# Gate_main.net
KiCad netlist of a schematic drawn in EAGLE
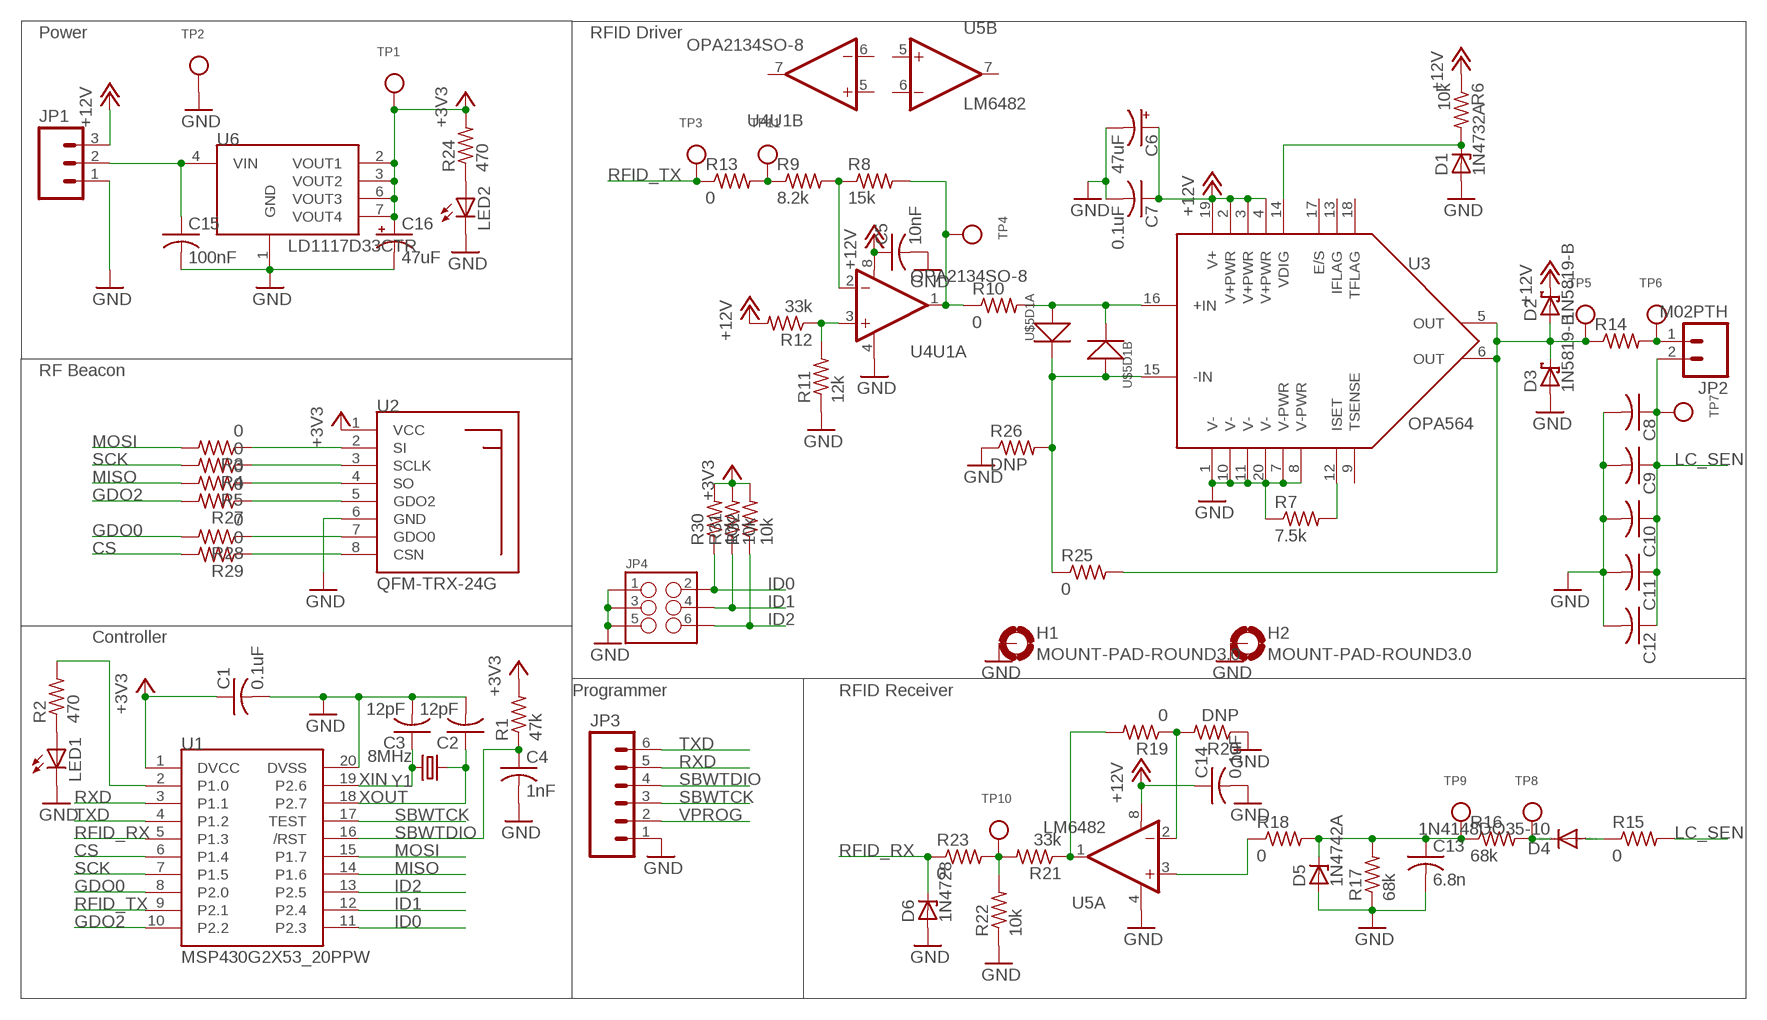
[diagram p0: schematic, sheet 1]

(export (version "E")
  (design (tool "Eeschema 10.0.6"))
  (components
    (comp (ref "C1")
      (value "0.1uF")
      (footprint "eagle-import:C0805")
      (libsource (lib "eagle-import") (part "C-USC0805"))
    )
    (comp (ref "C2")
      (value "12pF")
      (footprint "eagle-import:C0805")
      (libsource (lib "eagle-import") (part "C-USC0805"))
    )
    (comp (ref "C3")
      (value "12pF")
      (footprint "eagle-import:C0805")
      (libsource (lib "eagle-import") (part "C-USC0805"))
    )
    (comp (ref "C4")
      (value "1nF")
      (footprint "eagle-import:C0805")
      (libsource (lib "eagle-import") (part "C-USC0805"))
    )
    (comp (ref "C5")
      (value "10nF")
      (footprint "eagle-import:C0805")
      (libsource (lib "eagle-import") (part "C-USC0805"))
    )
    (comp (ref "C6")
      (value "47uF")
      (footprint "eagle-import:E2,5-6")
      (libsource (lib "eagle-import") (part "CPOL-USE2.5-6"))
    )
    (comp (ref "C7")
      (value "0.1uF")
      (footprint "eagle-import:C0805")
      (libsource (lib "eagle-import") (part "C-USC0805"))
    )
    (comp (ref "C8")
      (value "C-USC0805")
      (footprint "eagle-import:C0805")
      (libsource (lib "eagle-import") (part "C-USC0805"))
    )
    (comp (ref "C9")
      (value "C-USC0805")
      (footprint "eagle-import:C0805")
      (libsource (lib "eagle-import") (part "C-USC0805"))
    )
    (comp (ref "C10")
      (value "C-USC0805")
      (footprint "eagle-import:C0805")
      (libsource (lib "eagle-import") (part "C-USC0805"))
    )
    (comp (ref "C11")
      (value "C-USC0805")
      (footprint "eagle-import:C0805")
      (libsource (lib "eagle-import") (part "C-USC0805"))
    )
    (comp (ref "C12")
      (value "C-USC0805")
      (footprint "eagle-import:C0805")
      (libsource (lib "eagle-import") (part "C-USC0805"))
    )
    (comp (ref "C13")
      (value "6.8n")
      (footprint "eagle-import:C0805")
      (libsource (lib "eagle-import") (part "C-USC0805"))
    )
    (comp (ref "C14")
      (value "0.1uF")
      (footprint "eagle-import:C0805")
      (libsource (lib "eagle-import") (part "C-USC0805"))
    )
    (comp (ref "C15")
      (value "100nF")
      (footprint "eagle-import:C0805")
      (libsource (lib "eagle-import") (part "C-USC0805"))
    )
    (comp (ref "C16")
      (value "47uF")
      (footprint "eagle-import:E2,5-6")
      (libsource (lib "eagle-import") (part "CPOL-USE2.5-6"))
    )
    (comp (ref "D1")
      (value "1N4732A")
      (footprint "eagle-import:DO41Z10")
      (libsource (lib "eagle-import") (part "1N4728"))
    )
    (comp (ref "D2")
      (value "1N5819-B")
      (footprint "eagle-import:DO41-7.6")
      (libsource (lib "eagle-import") (part "1N5819-B"))
    )
    (comp (ref "D3")
      (value "1N5819-B")
      (footprint "eagle-import:DO41-7.6")
      (libsource (lib "eagle-import") (part "1N5819-B"))
    )
    (comp (ref "D4")
      (value "1N4148DO35-10")
      (footprint "eagle-import:DO35-10")
      (libsource (lib "eagle-import") (part "1N4148DO35-10"))
    )
    (comp (ref "D5")
      (value "1N4742A")
      (footprint "eagle-import:DO41Z10")
      (libsource (lib "eagle-import") (part "1N4728"))
    )
    (comp (ref "D6")
      (value "1N4728")
      (footprint "eagle-import:DO41Z10")
      (libsource (lib "eagle-import") (part "1N4728"))
    )
    (comp (ref "H1")
      (value "MOUNT-PAD-ROUND3.0")
      (footprint "eagle-import:3,0-PAD")
      (libsource (lib "eagle-import") (part "MOUNT-PAD-ROUND3.0"))
    )
    (comp (ref "H2")
      (value "MOUNT-PAD-ROUND3.0")
      (footprint "eagle-import:3,0-PAD")
      (libsource (lib "eagle-import") (part "MOUNT-PAD-ROUND3.0"))
    )
    (comp (ref "JP1")
      (value "M03PTH")
      (footprint "eagle-import:1X03")
      (libsource (lib "eagle-import") (part "M03PTH"))
    )
    (comp (ref "JP2")
      (value "M02PTH")
      (footprint "eagle-import:1X02")
      (libsource (lib "eagle-import") (part "M02PTH"))
    )
    (comp (ref "JP3")
      (value "M06SIP")
      (footprint "eagle-import:1X06")
      (libsource (lib "eagle-import") (part "M06SIP"))
    )
    (comp (ref "JP4")
      (value "M03X22X3_SILK_SM")
      (footprint "eagle-import:2X3")
      (libsource (lib "eagle-import") (part "M03X22X3_SILK_SM"))
    )
    (comp (ref "LED1")
      (value "LEDCHIPLED_0603")
      (footprint "eagle-import:CHIPLED_0603")
      (libsource (lib "eagle-import") (part "LEDCHIPLED_0603"))
    )
    (comp (ref "LED2")
      (value "LEDCHIPLED_0603")
      (footprint "eagle-import:CHIPLED_0603")
      (libsource (lib "eagle-import") (part "LEDCHIPLED_0603"))
    )
    (comp (ref "R1")
      (value "47k")
      (footprint "eagle-import:R0805")
      (libsource (lib "eagle-import") (part "R-US_R0805"))
    )
    (comp (ref "R2")
      (value "470")
      (footprint "eagle-import:R0805")
      (libsource (lib "eagle-import") (part "R-US_R0805"))
    )
    (comp (ref "R3")
      (value "0")
      (footprint "eagle-import:R0805")
      (libsource (lib "eagle-import") (part "R-US_R0805"))
    )
    (comp (ref "R4")
      (value "0")
      (footprint "eagle-import:R0805")
      (libsource (lib "eagle-import") (part "R-US_R0805"))
    )
    (comp (ref "R5")
      (value "0")
      (footprint "eagle-import:R0805")
      (libsource (lib "eagle-import") (part "R-US_R0805"))
    )
    (comp (ref "R6")
      (value "10k")
      (footprint "eagle-import:R0805")
      (libsource (lib "eagle-import") (part "R-US_R0805"))
    )
    (comp (ref "R7")
      (value "7.5k")
      (footprint "eagle-import:R0805")
      (libsource (lib "eagle-import") (part "R-US_R0805"))
    )
    (comp (ref "R8")
      (value "15k")
      (footprint "eagle-import:R0805")
      (libsource (lib "eagle-import") (part "R-US_R0805"))
    )
    (comp (ref "R9")
      (value "8.2k")
      (footprint "eagle-import:R0805")
      (libsource (lib "eagle-import") (part "R-US_R0805"))
    )
    (comp (ref "R10")
      (value "0")
      (footprint "eagle-import:R0805")
      (libsource (lib "eagle-import") (part "R-US_R0805"))
    )
    (comp (ref "R11")
      (value "12k")
      (footprint "eagle-import:R0805")
      (libsource (lib "eagle-import") (part "R-US_R0805"))
    )
    (comp (ref "R12")
      (value "33k")
      (footprint "eagle-import:R0805")
      (libsource (lib "eagle-import") (part "R-US_R0805"))
    )
    (comp (ref "R13")
      (value "0")
      (footprint "eagle-import:R0805")
      (libsource (lib "eagle-import") (part "R-US_R0805"))
    )
    (comp (ref "R14")
      (value "R-US_0207/10")
      (footprint "eagle-import:0207_10")
      (libsource (lib "eagle-import") (part "R-US_0207/10"))
    )
    (comp (ref "R15")
      (value "0")
      (footprint "eagle-import:R0805")
      (libsource (lib "eagle-import") (part "R-US_R0805"))
    )
    (comp (ref "R16")
      (value "68k")
      (footprint "eagle-import:R0805")
      (libsource (lib "eagle-import") (part "R-US_R0805"))
    )
    (comp (ref "R17")
      (value "68k")
      (footprint "eagle-import:R0805")
      (libsource (lib "eagle-import") (part "R-US_R0805"))
    )
    (comp (ref "R18")
      (value "0")
      (footprint "eagle-import:R0805")
      (libsource (lib "eagle-import") (part "R-US_R0805"))
    )
    (comp (ref "R19")
      (value "0")
      (footprint "eagle-import:R0805")
      (libsource (lib "eagle-import") (part "R-US_R0805"))
    )
    (comp (ref "R20")
      (value "DNP")
      (footprint "eagle-import:R0805")
      (libsource (lib "eagle-import") (part "R-US_R0805"))
    )
    (comp (ref "R21")
      (value "33k")
      (footprint "eagle-import:R0805")
      (libsource (lib "eagle-import") (part "R-US_R0805"))
    )
    (comp (ref "R22")
      (value "10k")
      (footprint "eagle-import:R0805")
      (libsource (lib "eagle-import") (part "R-US_R0805"))
    )
    (comp (ref "R23")
      (value "0")
      (footprint "eagle-import:R0805")
      (libsource (lib "eagle-import") (part "R-US_R0805"))
    )
    (comp (ref "R24")
      (value "470")
      (footprint "eagle-import:R0805")
      (libsource (lib "eagle-import") (part "R-US_R0805"))
    )
    (comp (ref "R25")
      (value "0")
      (footprint "eagle-import:R0805")
      (libsource (lib "eagle-import") (part "R-US_R0805"))
    )
    (comp (ref "R26")
      (value "DNP")
      (footprint "eagle-import:R0805")
      (libsource (lib "eagle-import") (part "R-US_R0805"))
    )
    (comp (ref "R27")
      (value "0")
      (footprint "eagle-import:R0805")
      (libsource (lib "eagle-import") (part "R-US_R0805"))
    )
    (comp (ref "R28")
      (value "0")
      (footprint "eagle-import:R0805")
      (libsource (lib "eagle-import") (part "R-US_R0805"))
    )
    (comp (ref "R29")
      (value "0")
      (footprint "eagle-import:R0805")
      (libsource (lib "eagle-import") (part "R-US_R0805"))
    )
    (comp (ref "R30")
      (value "10k")
      (footprint "eagle-import:R0805")
      (libsource (lib "eagle-import") (part "R-US_R0805"))
    )
    (comp (ref "R31")
      (value "10k")
      (footprint "eagle-import:R0805")
      (libsource (lib "eagle-import") (part "R-US_R0805"))
    )
    (comp (ref "R32")
      (value "10k")
      (footprint "eagle-import:R0805")
      (libsource (lib "eagle-import") (part "R-US_R0805"))
    )
    (comp (ref "TP1")
      (value "TESTPOINT0.1\"")
      (footprint "eagle-import:1X01_ROUND")
      (libsource (lib "eagle-import") (part "TESTPOINT0.1{dblquote}"))
    )
    (comp (ref "TP2")
      (value "TESTPOINT0.1\"")
      (footprint "eagle-import:1X01_ROUND")
      (libsource (lib "eagle-import") (part "TESTPOINT0.1{dblquote}"))
    )
    (comp (ref "TP3")
      (value "TESTPOINT0.1\"")
      (footprint "eagle-import:1X01_ROUND")
      (libsource (lib "eagle-import") (part "TESTPOINT0.1{dblquote}"))
    )
    (comp (ref "TP4")
      (value "TESTPOINT0.1\"")
      (footprint "eagle-import:1X01_ROUND")
      (libsource (lib "eagle-import") (part "TESTPOINT0.1{dblquote}"))
    )
    (comp (ref "TP5")
      (value "TESTPOINT0.1\"")
      (footprint "eagle-import:1X01_ROUND")
      (libsource (lib "eagle-import") (part "TESTPOINT0.1{dblquote}"))
    )
    (comp (ref "TP6")
      (value "TESTPOINT0.1\"")
      (footprint "eagle-import:1X01_ROUND")
      (libsource (lib "eagle-import") (part "TESTPOINT0.1{dblquote}"))
    )
    (comp (ref "TP7")
      (value "TESTPOINT0.1\"")
      (footprint "eagle-import:1X01_ROUND")
      (libsource (lib "eagle-import") (part "TESTPOINT0.1{dblquote}"))
    )
    (comp (ref "TP8")
      (value "TESTPOINT0.1\"")
      (footprint "eagle-import:1X01_ROUND")
      (libsource (lib "eagle-import") (part "TESTPOINT0.1{dblquote}"))
    )
    (comp (ref "TP9")
      (value "TESTPOINT0.1\"")
      (footprint "eagle-import:1X01_ROUND")
      (libsource (lib "eagle-import") (part "TESTPOINT0.1{dblquote}"))
    )
    (comp (ref "TP10")
      (value "TESTPOINT0.1\"")
      (footprint "eagle-import:1X01_ROUND")
      (libsource (lib "eagle-import") (part "TESTPOINT0.1{dblquote}"))
    )
    (comp (ref "TP11")
      (value "TESTPOINT0.1\"")
      (footprint "eagle-import:1X01_ROUND")
      (libsource (lib "eagle-import") (part "TESTPOINT0.1{dblquote}"))
    )
    (comp (ref "U$5")
      (value "SMS3922-015LF")
      (footprint "eagle-import:SMS3922-015LF")
      (libsource (lib "eagle-import") (part "SMS3922-015LF"))
    )
    (comp (ref "U1")
      (value "MSP430G2X53_20PPW")
      (footprint "eagle-import:PW(R-PDSO-G20)")
      (libsource (lib "eagle-import") (part "MSP430G2X53_20PPW"))
    )
    (comp (ref "U2")
      (value "QFM-TRX-24G")
      (footprint "eagle-import:QFM-TRX1-24G")
      (libsource (lib "eagle-import") (part "QFM-TRX-24G"))
    )
    (comp (ref "U3")
      (value "OPA564")
      (footprint "eagle-import:SO-20LD")
      (libsource (lib "eagle-import") (part "OPA564"))
    )
    (comp (ref "U4")
      (value "OPA2134SO-8")
      (footprint "eagle-import:SOIC8")
      (libsource (lib "eagle-import") (part "OPA2134SO-8"))
    )
    (comp (ref "U5")
      (value "LM6482")
      (footprint "eagle-import:SOIC8")
      (libsource (lib "eagle-import") (part "LM6482"))
    )
    (comp (ref "U6")
      (value "LD1117D33CTR")
      (footprint "eagle-import:SOIC8")
      (libsource (lib "eagle-import") (part "LD1117D33CTR"))
    )
    (comp (ref "Y1")
      (value "8MHz")
      (footprint "eagle-import:HC49U-V")
      (libsource (lib "eagle-import") (part "CRYSTALHC49UV"))
    )
  )
  (nets
    (net (code "1") (name "+3V3") (class "Default")
      (node (ref "C1") (pin "1") (pinfunction "1_1") (pintype "passive"))
      (node (ref "C16") (pin "+") (pinfunction "+_+") (pintype "passive"))
      (node (ref "R1") (pin "2") (pinfunction "2_2") (pintype "passive"))
      (node (ref "R24") (pin "2") (pinfunction "2_2") (pintype "passive"))
      (node (ref "R30") (pin "2") (pinfunction "2_2") (pintype "passive"))
      (node (ref "R31") (pin "2") (pinfunction "2_2") (pintype "passive"))
      (node (ref "R32") (pin "2") (pinfunction "2_2") (pintype "passive"))
      (node (ref "TP1") (pin "1") (pinfunction "P$1_1") (pintype "bidirectional"))
      (node (ref "U1") (pin "1") (pinfunction "DVCC_1") (pintype "bidirectional"))
      (node (ref "U2") (pin "1") (pinfunction "VCC_1") (pintype "bidirectional"))
      (node (ref "U6") (pin "2") (pinfunction "VOUT1_2") (pintype "bidirectional"))
      (node (ref "U6") (pin "3") (pinfunction "VOUT2_3") (pintype "bidirectional"))
      (node (ref "U6") (pin "6") (pinfunction "VOUT3_6") (pintype "bidirectional"))
      (node (ref "U6") (pin "7") (pinfunction "VOUT4_7") (pintype "bidirectional"))
    )
    (net (code "2") (name "+12V") (class "Default")
      (node (ref "C14") (pin "1") (pinfunction "1_1") (pintype "passive"))
      (node (ref "C5") (pin "1") (pinfunction "1_1") (pintype "passive"))
      (node (ref "C6") (pin "+") (pinfunction "+_+") (pintype "passive"))
      (node (ref "C7") (pin "1") (pinfunction "1_1") (pintype "passive"))
      (node (ref "D2") (pin "C") (pinfunction "C_C") (pintype "passive"))
      (node (ref "JP1") (pin "3") (pinfunction "3_3") (pintype "passive"))
      (node (ref "R12") (pin "2") (pinfunction "2_2") (pintype "passive"))
      (node (ref "R6") (pin "1") (pinfunction "1_1") (pintype "passive"))
      (node (ref "U3") (pin "19") (pinfunction "V+_19") (pintype "bidirectional"))
      (node (ref "U3") (pin "2") (pinfunction "V+PWR_2") (pintype "bidirectional"))
      (node (ref "U3") (pin "3") (pinfunction "V+PWR_3") (pintype "bidirectional"))
      (node (ref "U3") (pin "4") (pinfunction "V+PWR_4") (pintype "bidirectional"))
      (node (ref "U4") (pin "8") (pinfunction "V+_8") (pintype "power_in"))
      (node (ref "U5") (pin "8") (pinfunction "V+_8") (pintype "power_in"))
    )
    (net (code "3") (name "/CS") (class "Default")
      (node (ref "R29") (pin "2") (pinfunction "2_2") (pintype "passive"))
      (node (ref "U1") (pin "6") (pinfunction "P1.4_6") (pintype "bidirectional"))
    )
    (net (code "4") (name "/GDO0") (class "Default")
      (node (ref "R28") (pin "2") (pinfunction "2_2") (pintype "passive"))
      (node (ref "U1") (pin "8") (pinfunction "P2.0_8") (pintype "bidirectional"))
    )
    (net (code "5") (name "/GDO2") (class "Default")
      (node (ref "R27") (pin "2") (pinfunction "2_2") (pintype "passive"))
      (node (ref "U1") (pin "10") (pinfunction "P2.2_10") (pintype "bidirectional"))
    )
    (net (code "6") (name "/ID0") (class "Default")
      (node (ref "JP4") (pin "2") (pinfunction "2_2") (pintype "bidirectional"))
      (node (ref "R30") (pin "1") (pinfunction "1_1") (pintype "passive"))
      (node (ref "U1") (pin "11") (pinfunction "P2.3_11") (pintype "bidirectional"))
    )
    (net (code "7") (name "/ID1") (class "Default")
      (node (ref "JP4") (pin "4") (pinfunction "4_4") (pintype "bidirectional"))
      (node (ref "R31") (pin "1") (pinfunction "1_1") (pintype "passive"))
      (node (ref "U1") (pin "12") (pinfunction "P2.4_12") (pintype "bidirectional"))
    )
    (net (code "8") (name "/ID2") (class "Default")
      (node (ref "JP4") (pin "6") (pinfunction "6_6") (pintype "bidirectional"))
      (node (ref "R32") (pin "1") (pinfunction "1_1") (pintype "passive"))
      (node (ref "U1") (pin "13") (pinfunction "P2.5_13") (pintype "bidirectional"))
    )
    (net (code "9") (name "/LC_SEN") (class "Default")
      (node (ref "C10") (pin "1") (pinfunction "1_1") (pintype "passive"))
      (node (ref "C11") (pin "1") (pinfunction "1_1") (pintype "passive"))
      (node (ref "C12") (pin "1") (pinfunction "1_1") (pintype "passive"))
      (node (ref "C8") (pin "1") (pinfunction "1_1") (pintype "passive"))
      (node (ref "C9") (pin "1") (pinfunction "1_1") (pintype "passive"))
      (node (ref "JP2") (pin "2") (pinfunction "2_2") (pintype "passive"))
      (node (ref "R15") (pin "2") (pinfunction "2_2") (pintype "passive"))
      (node (ref "TP7") (pin "1") (pinfunction "P$1_1") (pintype "bidirectional"))
    )
    (net (code "10") (name "/MISO") (class "Default")
      (node (ref "R5") (pin "2") (pinfunction "2_2") (pintype "passive"))
      (node (ref "U1") (pin "14") (pinfunction "P1.6_14") (pintype "bidirectional"))
    )
    (net (code "11") (name "/MOSI") (class "Default")
      (node (ref "R3") (pin "2") (pinfunction "2_2") (pintype "passive"))
      (node (ref "U1") (pin "15") (pinfunction "P1.7_15") (pintype "bidirectional"))
    )
    (net (code "12") (name "/RFID_RX") (class "Default")
      (node (ref "D6") (pin "C") (pinfunction "C_C") (pintype "passive"))
      (node (ref "R23") (pin "1") (pinfunction "1_1") (pintype "passive"))
      (node (ref "U1") (pin "5") (pinfunction "P1.3_5") (pintype "bidirectional"))
    )
    (net (code "13") (name "/RFID_TX") (class "Default")
      (node (ref "R13") (pin "1") (pinfunction "1_1") (pintype "passive"))
      (node (ref "TP3") (pin "1") (pinfunction "P$1_1") (pintype "bidirectional"))
      (node (ref "U1") (pin "9") (pinfunction "P2.1_9") (pintype "bidirectional"))
    )
    (net (code "14") (name "/RXD") (class "Default")
      (node (ref "JP3") (pin "5") (pinfunction "5_5") (pintype "passive"))
      (node (ref "U1") (pin "3") (pinfunction "P1.1_3") (pintype "bidirectional"))
    )
    (net (code "15") (name "/SBWTCK") (class "Default")
      (node (ref "JP3") (pin "3") (pinfunction "3_3") (pintype "passive"))
      (node (ref "U1") (pin "17") (pinfunction "TEST_17") (pintype "bidirectional"))
    )
    (net (code "16") (name "/SBWTDIO") (class "Default")
      (node (ref "C4") (pin "1") (pinfunction "1_1") (pintype "passive"))
      (node (ref "JP3") (pin "4") (pinfunction "4_4") (pintype "passive"))
      (node (ref "R1") (pin "1") (pinfunction "1_1") (pintype "passive"))
      (node (ref "U1") (pin "16") (pinfunction "/RST_16") (pintype "bidirectional"))
    )
    (net (code "17") (name "/SCK") (class "Default")
      (node (ref "R4") (pin "2") (pinfunction "2_2") (pintype "passive"))
      (node (ref "U1") (pin "7") (pinfunction "P1.5_7") (pintype "bidirectional"))
    )
    (net (code "18") (name "/TXD") (class "Default")
      (node (ref "JP3") (pin "6") (pinfunction "6_6") (pintype "passive"))
      (node (ref "U1") (pin "4") (pinfunction "P1.2_4") (pintype "bidirectional"))
    )
    (net (code "19") (name "/VPROG") (class "Default")
      (node (ref "JP3") (pin "2") (pinfunction "2_2") (pintype "passive"))
    )
    (net (code "20") (name "/XIN") (class "Default")
      (node (ref "C3") (pin "1") (pinfunction "1_1") (pintype "passive"))
      (node (ref "U1") (pin "19") (pinfunction "P2.6_19") (pintype "bidirectional"))
      (node (ref "Y1") (pin "2") (pinfunction "2_2") (pintype "passive"))
    )
    (net (code "21") (name "/XOUT") (class "Default")
      (node (ref "C2") (pin "1") (pinfunction "1_1") (pintype "passive"))
      (node (ref "U1") (pin "18") (pinfunction "P2.7_18") (pintype "bidirectional"))
      (node (ref "Y1") (pin "1") (pinfunction "1_1") (pintype "passive"))
    )
    (net (code "22") (name "GND") (class "Default")
      (node (ref "C1") (pin "2") (pinfunction "2_2") (pintype "passive"))
      (node (ref "C10") (pin "2") (pinfunction "2_2") (pintype "passive"))
      (node (ref "C11") (pin "2") (pinfunction "2_2") (pintype "passive"))
      (node (ref "C12") (pin "2") (pinfunction "2_2") (pintype "passive"))
      (node (ref "C13") (pin "2") (pinfunction "2_2") (pintype "passive"))
      (node (ref "C14") (pin "2") (pinfunction "2_2") (pintype "passive"))
      (node (ref "C15") (pin "2") (pinfunction "2_2") (pintype "passive"))
      (node (ref "C16") (pin "-") (pinfunction "-_-") (pintype "passive"))
      (node (ref "C2") (pin "2") (pinfunction "2_2") (pintype "passive"))
      (node (ref "C3") (pin "2") (pinfunction "2_2") (pintype "passive"))
      (node (ref "C4") (pin "2") (pinfunction "2_2") (pintype "passive"))
      (node (ref "C5") (pin "2") (pinfunction "2_2") (pintype "passive"))
      (node (ref "C6") (pin "-") (pinfunction "-_-") (pintype "passive"))
      (node (ref "C7") (pin "2") (pinfunction "2_2") (pintype "passive"))
      (node (ref "C8") (pin "2") (pinfunction "2_2") (pintype "passive"))
      (node (ref "C9") (pin "2") (pinfunction "2_2") (pintype "passive"))
      (node (ref "D1") (pin "A") (pinfunction "A_A") (pintype "passive"))
      (node (ref "D3") (pin "A") (pinfunction "A_A") (pintype "passive"))
      (node (ref "D5") (pin "A") (pinfunction "A_A") (pintype "passive"))
      (node (ref "D6") (pin "A") (pinfunction "A_A") (pintype "passive"))
      (node (ref "H1") (pin "B3,0") (pinfunction "MOUNT_B3,0") (pintype "passive"))
      (node (ref "H2") (pin "B3,0") (pinfunction "MOUNT_B3,0") (pintype "passive"))
      (node (ref "JP1") (pin "1") (pinfunction "1_1") (pintype "passive"))
      (node (ref "JP3") (pin "1") (pinfunction "1_1") (pintype "passive"))
      (node (ref "JP4") (pin "1") (pinfunction "1_1") (pintype "bidirectional"))
      (node (ref "JP4") (pin "3") (pinfunction "3_3") (pintype "bidirectional"))
      (node (ref "JP4") (pin "5") (pinfunction "5_5") (pintype "bidirectional"))
      (node (ref "LED1") (pin "C") (pinfunction "C_C") (pintype "passive"))
      (node (ref "LED2") (pin "C") (pinfunction "C_C") (pintype "passive"))
      (node (ref "R11") (pin "1") (pinfunction "1_1") (pintype "passive"))
      (node (ref "R17") (pin "1") (pinfunction "1_1") (pintype "passive"))
      (node (ref "R20") (pin "1") (pinfunction "1_1") (pintype "passive"))
      (node (ref "R22") (pin "1") (pinfunction "1_1") (pintype "passive"))
      (node (ref "R26") (pin "1") (pinfunction "1_1") (pintype "passive"))
      (node (ref "R7") (pin "1") (pinfunction "1_1") (pintype "passive"))
      (node (ref "TP2") (pin "1") (pinfunction "P$1_1") (pintype "bidirectional"))
      (node (ref "U1") (pin "20") (pinfunction "DVSS_20") (pintype "bidirectional"))
      (node (ref "U2") (pin "6") (pinfunction "GND_6") (pintype "bidirectional"))
      (node (ref "U3") (pin "1") (pinfunction "V-_1") (pintype "bidirectional"))
      (node (ref "U3") (pin "10") (pinfunction "V-_10") (pintype "bidirectional"))
      (node (ref "U3") (pin "11") (pinfunction "V-_11") (pintype "bidirectional"))
      (node (ref "U3") (pin "20") (pinfunction "V-_20") (pintype "bidirectional"))
      (node (ref "U3") (pin "7") (pinfunction "V-PWR_7") (pintype "bidirectional"))
      (node (ref "U3") (pin "8") (pinfunction "V-PWR_8") (pintype "bidirectional"))
      (node (ref "U4") (pin "4") (pinfunction "V-_4") (pintype "power_in"))
      (node (ref "U5") (pin "4") (pinfunction "V-_4") (pintype "power_in"))
      (node (ref "U6") (pin "1") (pinfunction "GND_1") (pintype "bidirectional"))
    )
    (net (code "23") (name "Net-(D4-PadA)") (class "Default")
      (node (ref "D4") (pin "A") (pinfunction "A_A") (pintype "passive"))
      (node (ref "R15") (pin "1") (pinfunction "1_1") (pintype "passive"))
    )
    (net (code "24") (name "Net-(LED1-PadA)") (class "Default")
      (node (ref "LED1") (pin "A") (pinfunction "A_A") (pintype "passive"))
      (node (ref "R2") (pin "1") (pinfunction "1_1") (pintype "passive"))
    )
    (net (code "25") (name "Net-(LED2-PadA)") (class "Default")
      (node (ref "LED2") (pin "A") (pinfunction "A_A") (pintype "passive"))
      (node (ref "R24") (pin "1") (pinfunction "1_1") (pintype "passive"))
    )
    (net (code "26") (name "Net-(TP4-P$1)") (class "Default")
      (node (ref "R10") (pin "1") (pinfunction "1_1") (pintype "passive"))
      (node (ref "R8") (pin "2") (pinfunction "2_2") (pintype "passive"))
      (node (ref "TP4") (pin "1") (pinfunction "P$1_1") (pintype "bidirectional"))
      (node (ref "U4") (pin "1") (pinfunction "OUT_1") (pintype "output"))
    )
    (net (code "27") (name "Net-(TP5-P$1)") (class "Default")
      (node (ref "D2") (pin "A") (pinfunction "A_A") (pintype "passive"))
      (node (ref "D3") (pin "C") (pinfunction "C_C") (pintype "passive"))
      (node (ref "R14") (pin "1") (pinfunction "1_1") (pintype "passive"))
      (node (ref "R25") (pin "2") (pinfunction "2_2") (pintype "passive"))
      (node (ref "TP5") (pin "1") (pinfunction "P$1_1") (pintype "bidirectional"))
      (node (ref "U3") (pin "5") (pinfunction "OUT_5") (pintype "bidirectional"))
      (node (ref "U3") (pin "6") (pinfunction "OUT_6") (pintype "bidirectional"))
    )
    (net (code "28") (name "Net-(TP6-P$1)") (class "Default")
      (node (ref "JP2") (pin "1") (pinfunction "1_1") (pintype "passive"))
      (node (ref "R14") (pin "2") (pinfunction "2_2") (pintype "passive"))
      (node (ref "TP6") (pin "1") (pinfunction "P$1_1") (pintype "bidirectional"))
    )
    (net (code "29") (name "Net-(TP8-P$1)") (class "Default")
      (node (ref "D4") (pin "C") (pinfunction "C_C") (pintype "passive"))
      (node (ref "R16") (pin "2") (pinfunction "2_2") (pintype "passive"))
      (node (ref "TP8") (pin "1") (pinfunction "P$1_1") (pintype "bidirectional"))
    )
    (net (code "30") (name "Net-(TP9-P$1)") (class "Default")
      (node (ref "C13") (pin "1") (pinfunction "1_1") (pintype "passive"))
      (node (ref "D5") (pin "C") (pinfunction "C_C") (pintype "passive"))
      (node (ref "R16") (pin "1") (pinfunction "1_1") (pintype "passive"))
      (node (ref "R17") (pin "2") (pinfunction "2_2") (pintype "passive"))
      (node (ref "R18") (pin "2") (pinfunction "2_2") (pintype "passive"))
      (node (ref "TP9") (pin "1") (pinfunction "P$1_1") (pintype "bidirectional"))
    )
    (net (code "31") (name "Net-(TP10-P$1)") (class "Default")
      (node (ref "R21") (pin "2") (pinfunction "2_2") (pintype "passive"))
      (node (ref "R22") (pin "2") (pinfunction "2_2") (pintype "passive"))
      (node (ref "R23") (pin "2") (pinfunction "2_2") (pintype "passive"))
      (node (ref "TP10") (pin "1") (pinfunction "P$1_1") (pintype "bidirectional"))
    )
    (net (code "32") (name "Net-(TP11-P$1)") (class "Default")
      (node (ref "R13") (pin "2") (pinfunction "2_2") (pintype "passive"))
      (node (ref "R9") (pin "1") (pinfunction "1_1") (pintype "passive"))
      (node (ref "TP11") (pin "1") (pinfunction "P$1_1") (pintype "bidirectional"))
    )
    (net (code "33") (name "Net-(U$5A-A)") (class "Default")
      (node (ref "R10") (pin "2") (pinfunction "2_2") (pintype "passive"))
      (node (ref "U$5") (pin "2") (pinfunction "K_2") (pintype "bidirectional"))
      (node (ref "U$5") (pin "4") (pinfunction "A_4") (pintype "bidirectional"))
      (node (ref "U3") (pin "16") (pinfunction "+IN_16") (pintype "bidirectional"))
    )
    (net (code "34") (name "Net-(U$5A-K)") (class "Default")
      (node (ref "R25") (pin "1") (pinfunction "1_1") (pintype "passive"))
      (node (ref "R26") (pin "2") (pinfunction "2_2") (pintype "passive"))
      (node (ref "U$5") (pin "1") (pinfunction "K_1") (pintype "bidirectional"))
      (node (ref "U$5") (pin "3") (pinfunction "A_3") (pintype "bidirectional"))
      (node (ref "U3") (pin "15") (pinfunction "-IN_15") (pintype "bidirectional"))
    )
    (net (code "35") (name "Net-(U1-P1.0)") (class "Default")
      (node (ref "R2") (pin "2") (pinfunction "2_2") (pintype "passive"))
      (node (ref "U1") (pin "2") (pinfunction "P1.0_2") (pintype "bidirectional"))
    )
    (net (code "36") (name "Net-(U2-CSN)") (class "Default")
      (node (ref "R29") (pin "1") (pinfunction "1_1") (pintype "passive"))
      (node (ref "U2") (pin "8") (pinfunction "CSN_8") (pintype "bidirectional"))
    )
    (net (code "37") (name "Net-(U2-GDO0)") (class "Default")
      (node (ref "R28") (pin "1") (pinfunction "1_1") (pintype "passive"))
      (node (ref "U2") (pin "7") (pinfunction "GDO0_7") (pintype "bidirectional"))
    )
    (net (code "38") (name "Net-(U2-GDO2)") (class "Default")
      (node (ref "R27") (pin "1") (pinfunction "1_1") (pintype "passive"))
      (node (ref "U2") (pin "5") (pinfunction "GDO2_5") (pintype "bidirectional"))
    )
    (net (code "39") (name "Net-(U2-SCLK)") (class "Default")
      (node (ref "R4") (pin "1") (pinfunction "1_1") (pintype "passive"))
      (node (ref "U2") (pin "3") (pinfunction "SCLK_3") (pintype "bidirectional"))
    )
    (net (code "40") (name "Net-(U2-SI)") (class "Default")
      (node (ref "R3") (pin "1") (pinfunction "1_1") (pintype "passive"))
      (node (ref "U2") (pin "2") (pinfunction "SI_2") (pintype "bidirectional"))
    )
    (net (code "41") (name "Net-(U2-SO)") (class "Default")
      (node (ref "R5") (pin "1") (pinfunction "1_1") (pintype "passive"))
      (node (ref "U2") (pin "4") (pinfunction "SO_4") (pintype "bidirectional"))
    )
    (net (code "42") (name "Net-(U3-ISET)") (class "Default")
      (node (ref "R7") (pin "2") (pinfunction "2_2") (pintype "passive"))
      (node (ref "U3") (pin "12") (pinfunction "ISET_12") (pintype "bidirectional"))
    )
    (net (code "43") (name "Net-(U3-VDIG)") (class "Default")
      (node (ref "D1") (pin "C") (pinfunction "C_C") (pintype "passive"))
      (node (ref "R6") (pin "2") (pinfunction "2_2") (pintype "passive"))
      (node (ref "U3") (pin "14") (pinfunction "VDIG_14") (pintype "bidirectional"))
    )
    (net (code "44") (name "Net-(U4A-+IN)") (class "Default")
      (node (ref "R11") (pin "2") (pinfunction "2_2") (pintype "passive"))
      (node (ref "R12") (pin "1") (pinfunction "1_1") (pintype "passive"))
      (node (ref "U4") (pin "3") (pinfunction "+IN_3") (pintype "input"))
    )
    (net (code "45") (name "Net-(U4A--IN)") (class "Default")
      (node (ref "R8") (pin "1") (pinfunction "1_1") (pintype "passive"))
      (node (ref "R9") (pin "2") (pinfunction "2_2") (pintype "passive"))
      (node (ref "U4") (pin "2") (pinfunction "-IN_2") (pintype "input"))
    )
    (net (code "46") (name "Net-(U5A-+IN)") (class "Default")
      (node (ref "R18") (pin "1") (pinfunction "1_1") (pintype "passive"))
      (node (ref "U5") (pin "3") (pinfunction "+IN_3") (pintype "input"))
    )
    (net (code "47") (name "Net-(U5A--IN)") (class "Default")
      (node (ref "R19") (pin "1") (pinfunction "1_1") (pintype "passive"))
      (node (ref "R20") (pin "2") (pinfunction "2_2") (pintype "passive"))
      (node (ref "U5") (pin "2") (pinfunction "-IN_2") (pintype "input"))
    )
    (net (code "48") (name "Net-(U5A-OUT)") (class "Default")
      (node (ref "R19") (pin "2") (pinfunction "2_2") (pintype "passive"))
      (node (ref "R21") (pin "1") (pinfunction "1_1") (pintype "passive"))
      (node (ref "U5") (pin "1") (pinfunction "OUT_1") (pintype "output"))
    )
    (net (code "49") (name "Net-(U6-VIN)") (class "Default")
      (node (ref "C15") (pin "1") (pinfunction "1_1") (pintype "passive"))
      (node (ref "JP1") (pin "2") (pinfunction "2_2") (pintype "passive"))
      (node (ref "U6") (pin "4") (pinfunction "VIN_4") (pintype "bidirectional"))
    )
    (net (code "50") (name "unconnected-(U3-E{slash}S-Pad17)") (class "Default")
      (node (ref "U3") (pin "17") (pinfunction "E/S_17") (pintype "bidirectional"))
    )
    (net (code "51") (name "unconnected-(U3-IFLAG-Pad13)") (class "Default")
      (node (ref "U3") (pin "13") (pinfunction "IFLAG_13") (pintype "bidirectional"))
    )
    (net (code "52") (name "unconnected-(U3-TFLAG-Pad18)") (class "Default")
      (node (ref "U3") (pin "18") (pinfunction "TFLAG_18") (pintype "bidirectional"))
    )
    (net (code "53") (name "unconnected-(U3-TSENSE-Pad9)") (class "Default")
      (node (ref "U3") (pin "9") (pinfunction "TSENSE_9") (pintype "bidirectional"))
    )
    (net (code "54") (name "unconnected-(U4B-+IN-Pad5)") (class "Default")
      (node (ref "U4") (pin "5") (pinfunction "+IN_5") (pintype "input"))
    )
    (net (code "55") (name "unconnected-(U4B--IN-Pad6)") (class "Default")
      (node (ref "U4") (pin "6") (pinfunction "-IN_6") (pintype "input"))
    )
    (net (code "56") (name "unconnected-(U4B-OUT-Pad7)") (class "Default")
      (node (ref "U4") (pin "7") (pinfunction "OUT_7") (pintype "output"))
    )
    (net (code "57") (name "unconnected-(U5B-+IN-Pad5)") (class "Default")
      (node (ref "U5") (pin "5") (pinfunction "+IN_5") (pintype "input"))
    )
    (net (code "58") (name "unconnected-(U5B--IN-Pad6)") (class "Default")
      (node (ref "U5") (pin "6") (pinfunction "-IN_6") (pintype "input"))
    )
    (net (code "59") (name "unconnected-(U5B-OUT-Pad7)") (class "Default")
      (node (ref "U5") (pin "7") (pinfunction "OUT_7") (pintype "output"))
    )
  )
)
